# 2.net
KiCad netlist of a schematic drawn in Altium Designer
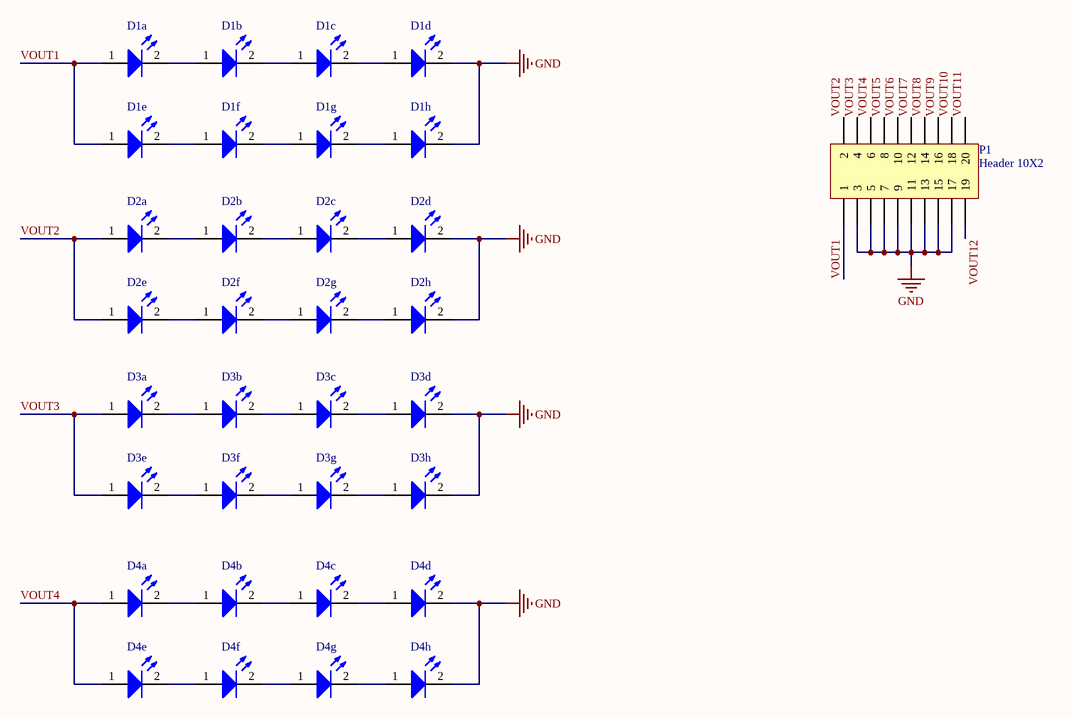
[diagram p0: 数粒机发射板2通道.SchDoc]

(export (version "E")
  (design (tool "Eeschema 10.0.6"))
  (components
    (comp (ref "D1a")
      (value "红外接收珠子")
      (footprint "EL-1KL3")
      (description "EL-1KL3")
      (fields (field (name "PUBLISHER") "Altium Limited"))
      (libsource (lib "Miscellaneous Devices") (part "EL-1KL3"))
    )
    (comp (ref "D1b")
      (value "红外接收珠子")
      (footprint "EL-1KL3")
      (description "EL-1KL3")
      (fields (field (name "PUBLISHER") "Altium Limited"))
      (libsource (lib "Miscellaneous Devices") (part "EL-1KL3"))
    )
    (comp (ref "D1c")
      (value "红外接收珠子")
      (footprint "EL-1KL3")
      (description "EL-1KL3")
      (fields (field (name "PUBLISHER") "Altium Limited"))
      (libsource (lib "Miscellaneous Devices") (part "EL-1KL3"))
    )
    (comp (ref "D1d")
      (value "红外接收珠子")
      (footprint "EL-1KL3")
      (description "EL-1KL3")
      (fields (field (name "PUBLISHER") "Altium Limited"))
      (libsource (lib "Miscellaneous Devices") (part "EL-1KL3"))
    )
    (comp (ref "D1e")
      (value "红外接收珠子")
      (footprint "EL-1KL3")
      (description "EL-1KL3")
      (fields (field (name "PUBLISHER") "Altium Limited"))
      (libsource (lib "Miscellaneous Devices") (part "EL-1KL3"))
    )
    (comp (ref "D1f")
      (value "红外接收珠子")
      (footprint "EL-1KL3")
      (description "EL-1KL3")
      (fields (field (name "PUBLISHER") "Altium Limited"))
      (libsource (lib "Miscellaneous Devices") (part "EL-1KL3"))
    )
    (comp (ref "D1g")
      (value "红外接收珠子")
      (footprint "EL-1KL3")
      (description "EL-1KL3")
      (fields (field (name "PUBLISHER") "Altium Limited"))
      (libsource (lib "Miscellaneous Devices") (part "EL-1KL3"))
    )
    (comp (ref "D1h")
      (value "红外接收珠子")
      (footprint "EL-1KL3")
      (description "EL-1KL3")
      (fields (field (name "PUBLISHER") "Altium Limited"))
      (libsource (lib "Miscellaneous Devices") (part "EL-1KL3"))
    )
    (comp (ref "D2a")
      (value "红外接收珠子")
      (footprint "EL-1KL3")
      (description "EL-1KL3")
      (fields (field (name "PUBLISHER") "Altium Limited"))
      (libsource (lib "Miscellaneous Devices") (part "EL-1KL3"))
    )
    (comp (ref "D2b")
      (value "红外接收珠子")
      (footprint "EL-1KL3")
      (description "EL-1KL3")
      (fields (field (name "PUBLISHER") "Altium Limited"))
      (libsource (lib "Miscellaneous Devices") (part "EL-1KL3"))
    )
    (comp (ref "D2c")
      (value "红外接收珠子")
      (footprint "EL-1KL3")
      (description "EL-1KL3")
      (fields (field (name "PUBLISHER") "Altium Limited"))
      (libsource (lib "Miscellaneous Devices") (part "EL-1KL3"))
    )
    (comp (ref "D2d")
      (value "红外接收珠子")
      (footprint "EL-1KL3")
      (description "EL-1KL3")
      (fields (field (name "PUBLISHER") "Altium Limited"))
      (libsource (lib "Miscellaneous Devices") (part "EL-1KL3"))
    )
    (comp (ref "D2e")
      (value "红外接收珠子")
      (footprint "EL-1KL3")
      (description "EL-1KL3")
      (fields (field (name "PUBLISHER") "Altium Limited"))
      (libsource (lib "Miscellaneous Devices") (part "EL-1KL3"))
    )
    (comp (ref "D2f")
      (value "红外接收珠子")
      (footprint "EL-1KL3")
      (description "EL-1KL3")
      (fields (field (name "PUBLISHER") "Altium Limited"))
      (libsource (lib "Miscellaneous Devices") (part "EL-1KL3"))
    )
    (comp (ref "D2g")
      (value "红外接收珠子")
      (footprint "EL-1KL3")
      (description "EL-1KL3")
      (fields (field (name "PUBLISHER") "Altium Limited"))
      (libsource (lib "Miscellaneous Devices") (part "EL-1KL3"))
    )
    (comp (ref "D2h")
      (value "红外接收珠子")
      (footprint "EL-1KL3")
      (description "EL-1KL3")
      (fields (field (name "PUBLISHER") "Altium Limited"))
      (libsource (lib "Miscellaneous Devices") (part "EL-1KL3"))
    )
    (comp (ref "D3a")
      (value "红外接收珠子")
      (footprint "EL-1KL3")
      (description "EL-1KL3")
      (fields (field (name "PUBLISHER") "Altium Limited"))
      (libsource (lib "Miscellaneous Devices") (part "EL-1KL3"))
    )
    (comp (ref "D3b")
      (value "红外接收珠子")
      (footprint "EL-1KL3")
      (description "EL-1KL3")
      (fields (field (name "PUBLISHER") "Altium Limited"))
      (libsource (lib "Miscellaneous Devices") (part "EL-1KL3"))
    )
    (comp (ref "D3c")
      (value "红外接收珠子")
      (footprint "EL-1KL3")
      (description "EL-1KL3")
      (fields (field (name "PUBLISHER") "Altium Limited"))
      (libsource (lib "Miscellaneous Devices") (part "EL-1KL3"))
    )
    (comp (ref "D3d")
      (value "红外接收珠子")
      (footprint "EL-1KL3")
      (description "EL-1KL3")
      (fields (field (name "PUBLISHER") "Altium Limited"))
      (libsource (lib "Miscellaneous Devices") (part "EL-1KL3"))
    )
    (comp (ref "D3e")
      (value "红外接收珠子")
      (footprint "EL-1KL3")
      (description "EL-1KL3")
      (fields (field (name "PUBLISHER") "Altium Limited"))
      (libsource (lib "Miscellaneous Devices") (part "EL-1KL3"))
    )
    (comp (ref "D3f")
      (value "红外接收珠子")
      (footprint "EL-1KL3")
      (description "EL-1KL3")
      (fields (field (name "PUBLISHER") "Altium Limited"))
      (libsource (lib "Miscellaneous Devices") (part "EL-1KL3"))
    )
    (comp (ref "D3g")
      (value "红外接收珠子")
      (footprint "EL-1KL3")
      (description "EL-1KL3")
      (fields (field (name "PUBLISHER") "Altium Limited"))
      (libsource (lib "Miscellaneous Devices") (part "EL-1KL3"))
    )
    (comp (ref "D3h")
      (value "红外接收珠子")
      (footprint "EL-1KL3")
      (description "EL-1KL3")
      (fields (field (name "PUBLISHER") "Altium Limited"))
      (libsource (lib "Miscellaneous Devices") (part "EL-1KL3"))
    )
    (comp (ref "D4a")
      (value "红外接收珠子")
      (footprint "EL-1KL3")
      (description "EL-1KL3")
      (fields (field (name "PUBLISHER") "Altium Limited"))
      (libsource (lib "Miscellaneous Devices") (part "EL-1KL3"))
    )
    (comp (ref "D4b")
      (value "红外接收珠子")
      (footprint "EL-1KL3")
      (description "EL-1KL3")
      (fields (field (name "PUBLISHER") "Altium Limited"))
      (libsource (lib "Miscellaneous Devices") (part "EL-1KL3"))
    )
    (comp (ref "D4c")
      (value "红外接收珠子")
      (footprint "EL-1KL3")
      (description "EL-1KL3")
      (fields (field (name "PUBLISHER") "Altium Limited"))
      (libsource (lib "Miscellaneous Devices") (part "EL-1KL3"))
    )
    (comp (ref "D4d")
      (value "红外接收珠子")
      (footprint "EL-1KL3")
      (description "EL-1KL3")
      (fields (field (name "PUBLISHER") "Altium Limited"))
      (libsource (lib "Miscellaneous Devices") (part "EL-1KL3"))
    )
    (comp (ref "D4e")
      (value "红外接收珠子")
      (footprint "EL-1KL3")
      (description "EL-1KL3")
      (fields (field (name "PUBLISHER") "Altium Limited"))
      (libsource (lib "Miscellaneous Devices") (part "EL-1KL3"))
    )
    (comp (ref "D4f")
      (value "红外接收珠子")
      (footprint "EL-1KL3")
      (description "EL-1KL3")
      (fields (field (name "PUBLISHER") "Altium Limited"))
      (libsource (lib "Miscellaneous Devices") (part "EL-1KL3"))
    )
    (comp (ref "D4g")
      (value "红外接收珠子")
      (footprint "EL-1KL3")
      (description "EL-1KL3")
      (fields (field (name "PUBLISHER") "Altium Limited"))
      (libsource (lib "Miscellaneous Devices") (part "EL-1KL3"))
    )
    (comp (ref "D4h")
      (value "红外接收珠子")
      (footprint "EL-1KL3")
      (description "EL-1KL3")
      (fields (field (name "PUBLISHER") "Altium Limited"))
      (libsource (lib "Miscellaneous Devices") (part "EL-1KL3"))
    )
    (comp (ref "P1")
      (value "Header 10X2")
      (footprint "niujiaocha20p")
      (description "Header, 10-Pin, Dual row")
      (fields (field (name "PUBLISHER") "Altium Limited"))
      (libsource (lib "Miscellaneous Connectors") (part "Header 10X2"))
    )
  )
  (nets
    (net (code "1") (name "/VOUT1") (class "Default")
      (node (ref "D1a") (pin "1") (pinfunction "A_1") (pintype "passive"))
      (node (ref "D1e") (pin "1") (pinfunction "A_1") (pintype "passive"))
      (node (ref "P1") (pin "1") (pinfunction "1_1") (pintype "passive"))
    )
    (net (code "2") (name "/VOUT2") (class "Default")
      (node (ref "D2a") (pin "1") (pinfunction "A_1") (pintype "passive"))
      (node (ref "D2e") (pin "1") (pinfunction "A_1") (pintype "passive"))
      (node (ref "P1") (pin "2") (pinfunction "2_2") (pintype "passive"))
    )
    (net (code "3") (name "/VOUT3") (class "Default")
      (node (ref "D3a") (pin "1") (pinfunction "A_1") (pintype "passive"))
      (node (ref "D3e") (pin "1") (pinfunction "A_1") (pintype "passive"))
      (node (ref "P1") (pin "4") (pinfunction "4_4") (pintype "passive"))
    )
    (net (code "4") (name "/VOUT4") (class "Default")
      (node (ref "D4a") (pin "1") (pinfunction "A_1") (pintype "passive"))
      (node (ref "D4e") (pin "1") (pinfunction "A_1") (pintype "passive"))
      (node (ref "P1") (pin "6") (pinfunction "6_6") (pintype "passive"))
    )
    (net (code "5") (name "/VOUT5") (class "Default")
      (node (ref "P1") (pin "8") (pinfunction "8_8") (pintype "passive"))
    )
    (net (code "6") (name "/VOUT6") (class "Default")
      (node (ref "P1") (pin "10") (pinfunction "10_10") (pintype "passive"))
    )
    (net (code "7") (name "/VOUT7") (class "Default")
      (node (ref "P1") (pin "12") (pinfunction "12_12") (pintype "passive"))
    )
    (net (code "8") (name "/VOUT8") (class "Default")
      (node (ref "P1") (pin "14") (pinfunction "14_14") (pintype "passive"))
    )
    (net (code "9") (name "/VOUT9") (class "Default")
      (node (ref "P1") (pin "16") (pinfunction "16_16") (pintype "passive"))
    )
    (net (code "10") (name "/VOUT10") (class "Default")
      (node (ref "P1") (pin "18") (pinfunction "18_18") (pintype "passive"))
    )
    (net (code "11") (name "/VOUT11") (class "Default")
      (node (ref "P1") (pin "20") (pinfunction "20_20") (pintype "passive"))
    )
    (net (code "12") (name "/VOUT12") (class "Default")
      (node (ref "P1") (pin "19") (pinfunction "19_19") (pintype "passive"))
    )
    (net (code "13") (name "GND") (class "Default")
      (node (ref "D1d") (pin "2") (pinfunction "K_2") (pintype "passive"))
      (node (ref "D1h") (pin "2") (pinfunction "K_2") (pintype "passive"))
      (node (ref "D2d") (pin "2") (pinfunction "K_2") (pintype "passive"))
      (node (ref "D2h") (pin "2") (pinfunction "K_2") (pintype "passive"))
      (node (ref "D3d") (pin "2") (pinfunction "K_2") (pintype "passive"))
      (node (ref "D3h") (pin "2") (pinfunction "K_2") (pintype "passive"))
      (node (ref "D4d") (pin "2") (pinfunction "K_2") (pintype "passive"))
      (node (ref "D4h") (pin "2") (pinfunction "K_2") (pintype "passive"))
      (node (ref "P1") (pin "11") (pinfunction "11_11") (pintype "passive"))
      (node (ref "P1") (pin "13") (pinfunction "13_13") (pintype "passive"))
      (node (ref "P1") (pin "15") (pinfunction "15_15") (pintype "passive"))
      (node (ref "P1") (pin "17") (pinfunction "17_17") (pintype "passive"))
      (node (ref "P1") (pin "3") (pinfunction "3_3") (pintype "passive"))
      (node (ref "P1") (pin "5") (pinfunction "5_5") (pintype "passive"))
      (node (ref "P1") (pin "7") (pinfunction "7_7") (pintype "passive"))
      (node (ref "P1") (pin "9") (pinfunction "9_9") (pintype "passive"))
    )
    (net (code "14") (name "Net-(D1a-K)") (class "Default")
      (node (ref "D1a") (pin "2") (pinfunction "K_2") (pintype "passive"))
      (node (ref "D1b") (pin "1") (pinfunction "A_1") (pintype "passive"))
    )
    (net (code "15") (name "Net-(D1b-K)") (class "Default")
      (node (ref "D1b") (pin "2") (pinfunction "K_2") (pintype "passive"))
      (node (ref "D1c") (pin "1") (pinfunction "A_1") (pintype "passive"))
    )
    (net (code "16") (name "Net-(D1c-K)") (class "Default")
      (node (ref "D1c") (pin "2") (pinfunction "K_2") (pintype "passive"))
      (node (ref "D1d") (pin "1") (pinfunction "A_1") (pintype "passive"))
    )
    (net (code "17") (name "Net-(D1e-K)") (class "Default")
      (node (ref "D1e") (pin "2") (pinfunction "K_2") (pintype "passive"))
      (node (ref "D1f") (pin "1") (pinfunction "A_1") (pintype "passive"))
    )
    (net (code "18") (name "Net-(D1f-K)") (class "Default")
      (node (ref "D1f") (pin "2") (pinfunction "K_2") (pintype "passive"))
      (node (ref "D1g") (pin "1") (pinfunction "A_1") (pintype "passive"))
    )
    (net (code "19") (name "Net-(D1g-K)") (class "Default")
      (node (ref "D1g") (pin "2") (pinfunction "K_2") (pintype "passive"))
      (node (ref "D1h") (pin "1") (pinfunction "A_1") (pintype "passive"))
    )
    (net (code "20") (name "Net-(D2a-K)") (class "Default")
      (node (ref "D2a") (pin "2") (pinfunction "K_2") (pintype "passive"))
      (node (ref "D2b") (pin "1") (pinfunction "A_1") (pintype "passive"))
    )
    (net (code "21") (name "Net-(D2b-K)") (class "Default")
      (node (ref "D2b") (pin "2") (pinfunction "K_2") (pintype "passive"))
      (node (ref "D2c") (pin "1") (pinfunction "A_1") (pintype "passive"))
    )
    (net (code "22") (name "Net-(D2c-K)") (class "Default")
      (node (ref "D2c") (pin "2") (pinfunction "K_2") (pintype "passive"))
      (node (ref "D2d") (pin "1") (pinfunction "A_1") (pintype "passive"))
    )
    (net (code "23") (name "Net-(D2e-K)") (class "Default")
      (node (ref "D2e") (pin "2") (pinfunction "K_2") (pintype "passive"))
      (node (ref "D2f") (pin "1") (pinfunction "A_1") (pintype "passive"))
    )
    (net (code "24") (name "Net-(D2f-K)") (class "Default")
      (node (ref "D2f") (pin "2") (pinfunction "K_2") (pintype "passive"))
      (node (ref "D2g") (pin "1") (pinfunction "A_1") (pintype "passive"))
    )
    (net (code "25") (name "Net-(D2g-K)") (class "Default")
      (node (ref "D2g") (pin "2") (pinfunction "K_2") (pintype "passive"))
      (node (ref "D2h") (pin "1") (pinfunction "A_1") (pintype "passive"))
    )
    (net (code "26") (name "Net-(D3a-K)") (class "Default")
      (node (ref "D3a") (pin "2") (pinfunction "K_2") (pintype "passive"))
      (node (ref "D3b") (pin "1") (pinfunction "A_1") (pintype "passive"))
    )
    (net (code "27") (name "Net-(D3b-K)") (class "Default")
      (node (ref "D3b") (pin "2") (pinfunction "K_2") (pintype "passive"))
      (node (ref "D3c") (pin "1") (pinfunction "A_1") (pintype "passive"))
    )
    (net (code "28") (name "Net-(D3c-K)") (class "Default")
      (node (ref "D3c") (pin "2") (pinfunction "K_2") (pintype "passive"))
      (node (ref "D3d") (pin "1") (pinfunction "A_1") (pintype "passive"))
    )
    (net (code "29") (name "Net-(D3e-K)") (class "Default")
      (node (ref "D3e") (pin "2") (pinfunction "K_2") (pintype "passive"))
      (node (ref "D3f") (pin "1") (pinfunction "A_1") (pintype "passive"))
    )
    (net (code "30") (name "Net-(D3f-K)") (class "Default")
      (node (ref "D3f") (pin "2") (pinfunction "K_2") (pintype "passive"))
      (node (ref "D3g") (pin "1") (pinfunction "A_1") (pintype "passive"))
    )
    (net (code "31") (name "Net-(D3g-K)") (class "Default")
      (node (ref "D3g") (pin "2") (pinfunction "K_2") (pintype "passive"))
      (node (ref "D3h") (pin "1") (pinfunction "A_1") (pintype "passive"))
    )
    (net (code "32") (name "Net-(D4a-K)") (class "Default")
      (node (ref "D4a") (pin "2") (pinfunction "K_2") (pintype "passive"))
      (node (ref "D4b") (pin "1") (pinfunction "A_1") (pintype "passive"))
    )
    (net (code "33") (name "Net-(D4b-K)") (class "Default")
      (node (ref "D4b") (pin "2") (pinfunction "K_2") (pintype "passive"))
      (node (ref "D4c") (pin "1") (pinfunction "A_1") (pintype "passive"))
    )
    (net (code "34") (name "Net-(D4c-K)") (class "Default")
      (node (ref "D4c") (pin "2") (pinfunction "K_2") (pintype "passive"))
      (node (ref "D4d") (pin "1") (pinfunction "A_1") (pintype "passive"))
    )
    (net (code "35") (name "Net-(D4e-K)") (class "Default")
      (node (ref "D4e") (pin "2") (pinfunction "K_2") (pintype "passive"))
      (node (ref "D4f") (pin "1") (pinfunction "A_1") (pintype "passive"))
    )
    (net (code "36") (name "Net-(D4f-K)") (class "Default")
      (node (ref "D4f") (pin "2") (pinfunction "K_2") (pintype "passive"))
      (node (ref "D4g") (pin "1") (pinfunction "A_1") (pintype "passive"))
    )
    (net (code "37") (name "Net-(D4g-K)") (class "Default")
      (node (ref "D4g") (pin "2") (pinfunction "K_2") (pintype "passive"))
      (node (ref "D4h") (pin "1") (pinfunction "A_1") (pintype "passive"))
    )
  )
)
